# ESP32_With_USB_C_3rd.net
KiCad netlist of a schematic drawn in Altium Designer
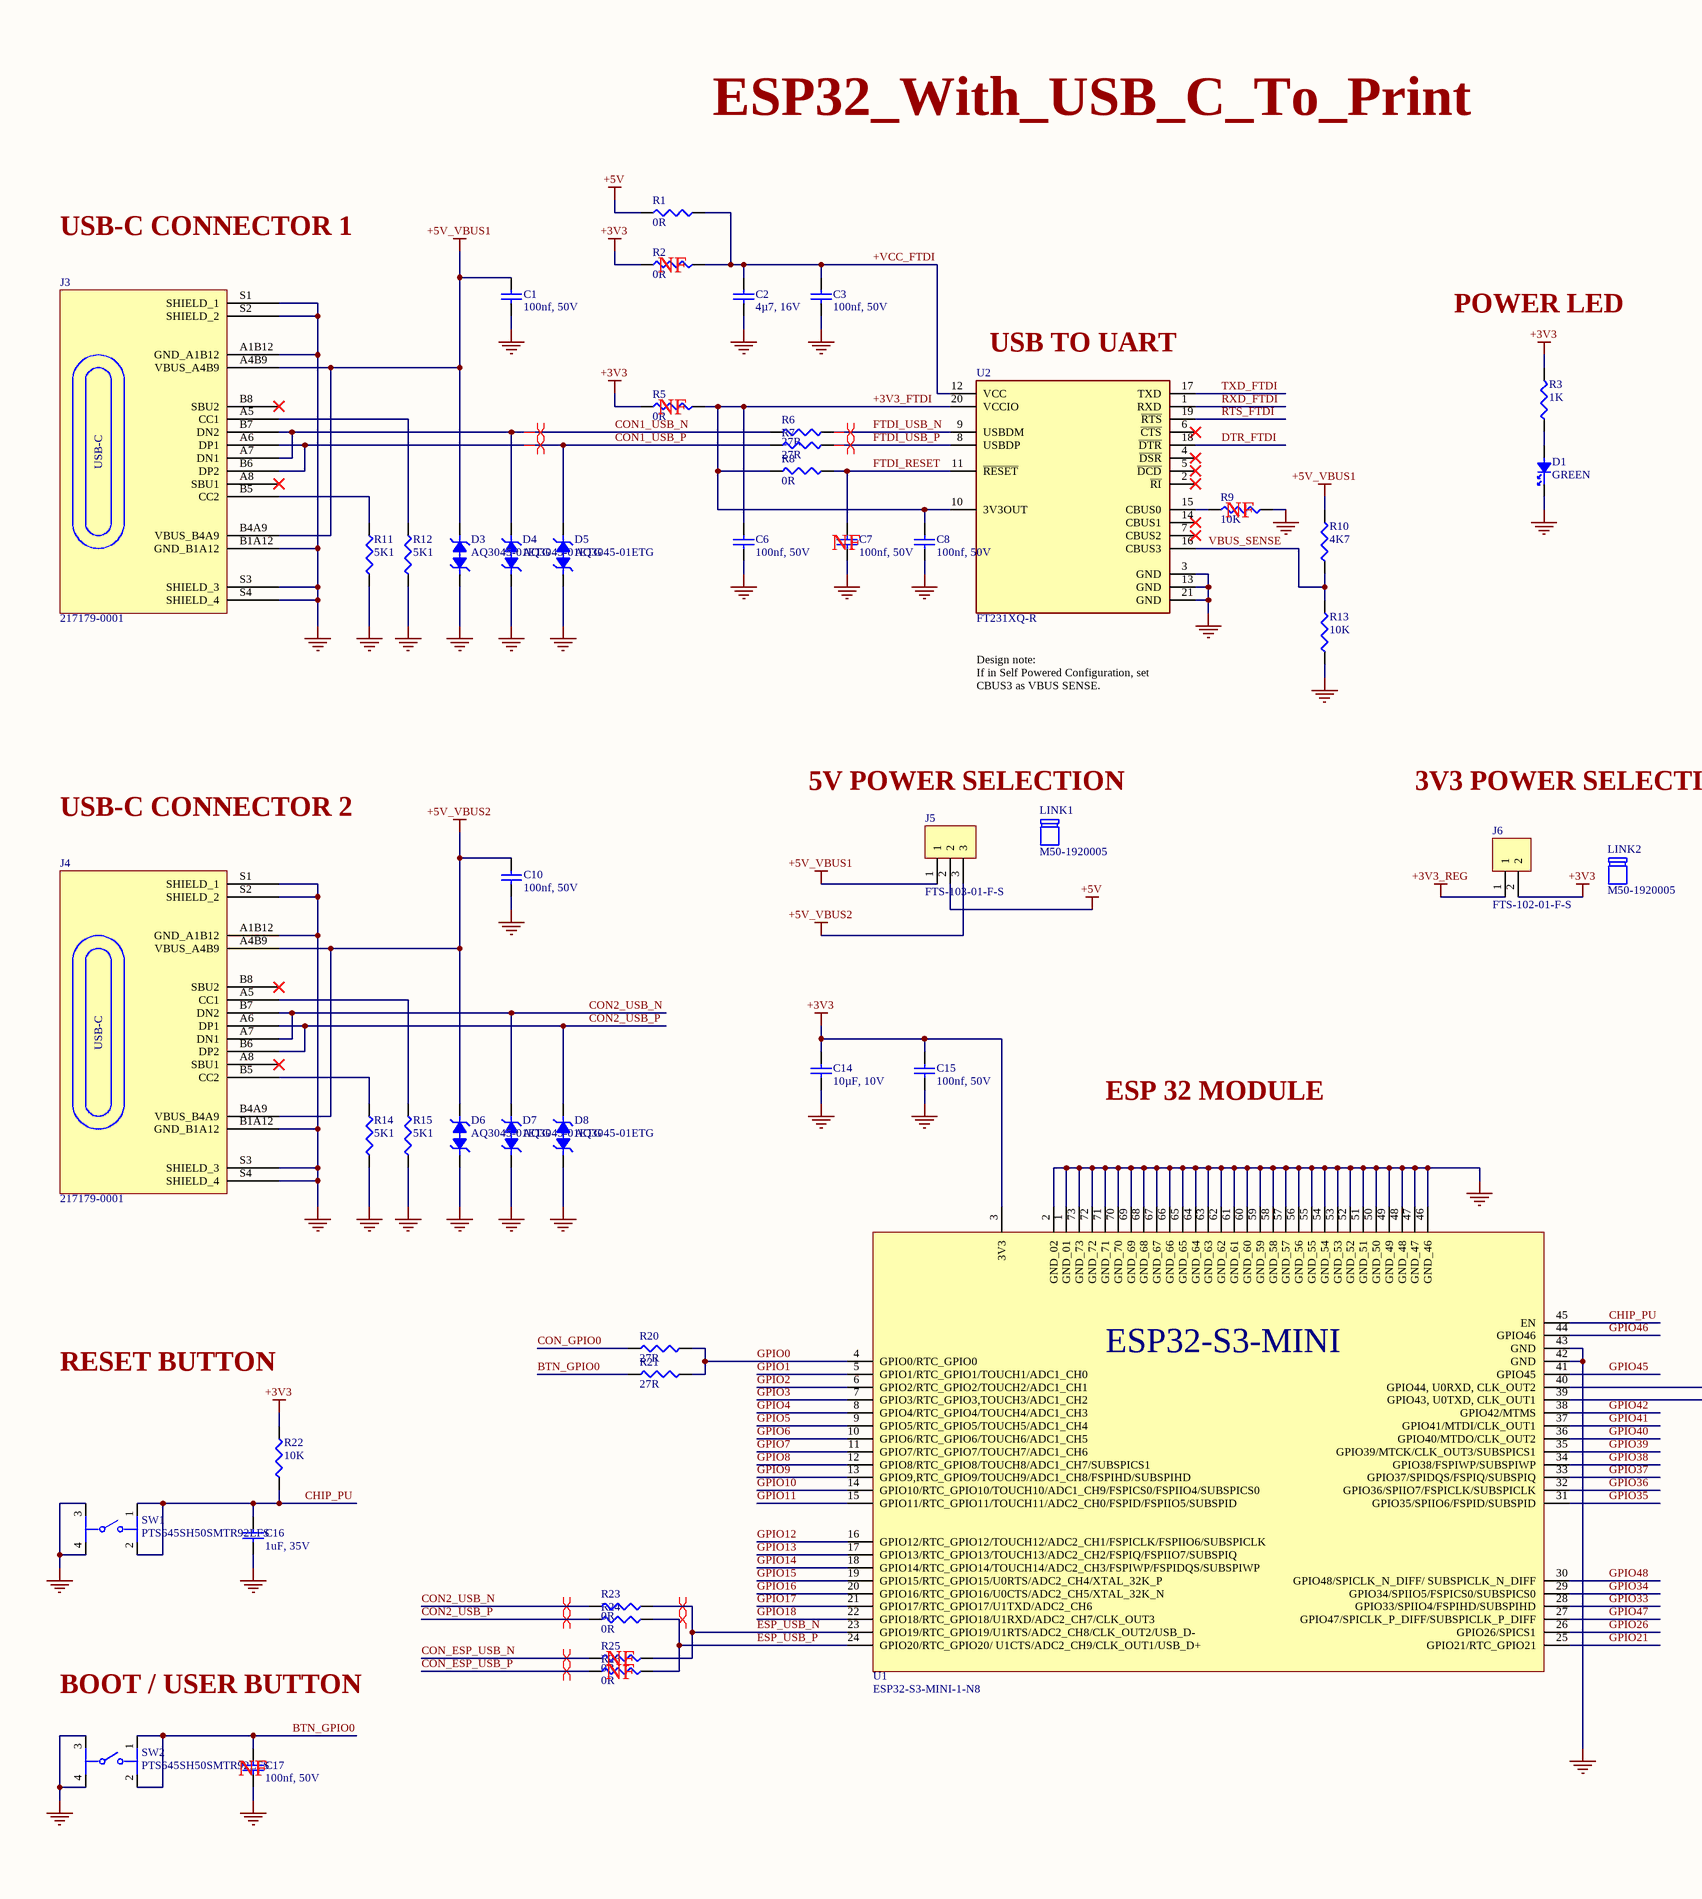
[diagram p0: ESP32 With USB C 3rd.SchDoc, left]
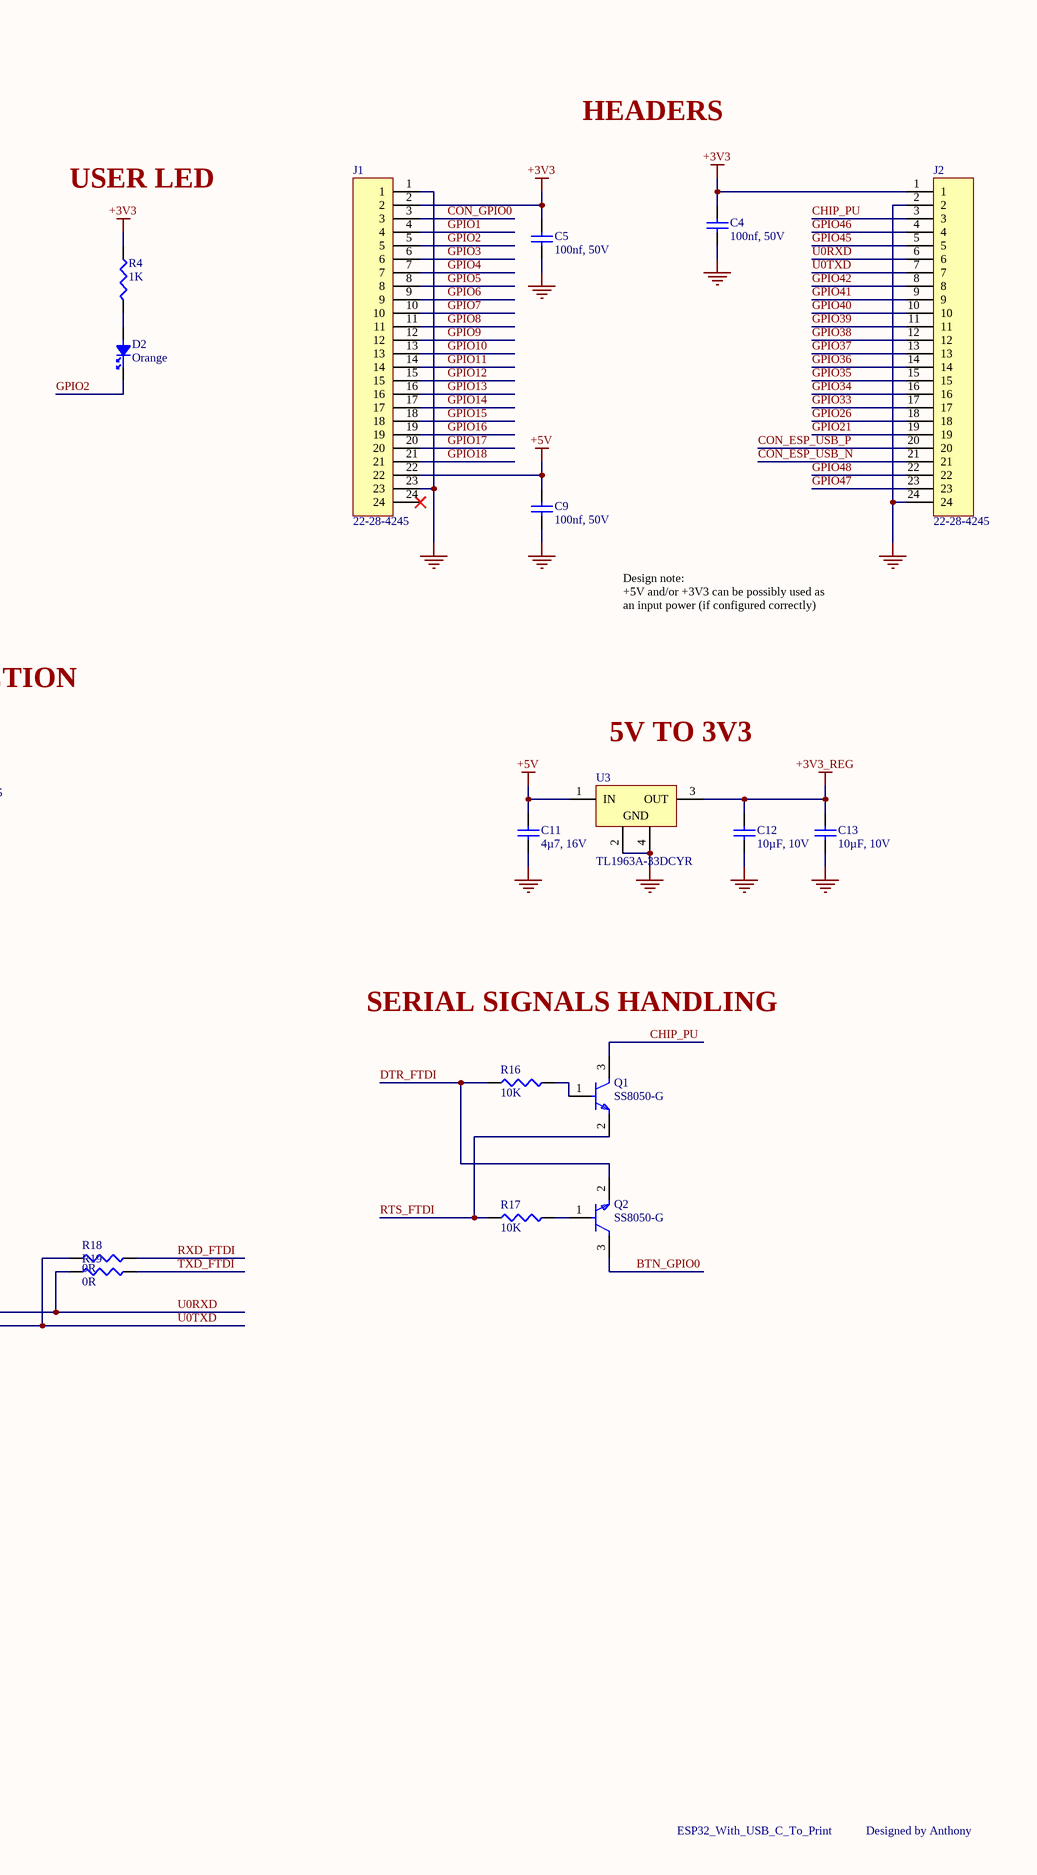
[diagram p1: ESP32 With USB C 3rd.SchDoc, right]

(export (version "E")
  (design (tool "Eeschema 10.0.6"))
  (components
    (comp (ref "C1")
      (value "100nf, 50V")
      (footprint "CAPC1005X65N")
      (description "CAP CER 0.1UF 50V X7R 0402")
      (fields
        (field (name "MANUFACTURER") "Samsung")
        (field (name "MANUFACTURER PART NUMBER") "CL05B104KB5NNNC")
      )
      (libsource (lib "Schlib1") (part "CL05B104KB5NNNC"))
    )
    (comp (ref "C2")
      (value "4µ7, 16V")
      (footprint "CAPC1005X65N")
      (description "CAP CER 4.7UF 16V X5R 0402")
      (fields
        (field (name "MANUFACTURER") "Samsung")
        (field (name "MANUFACTURER PART NUMBER") "CL05A475MO5NUNC")
      )
      (libsource (lib "Schlib1") (part "CL05A475MO5NUNC"))
    )
    (comp (ref "C3")
      (value "100nf, 50V")
      (footprint "CAPC1005X65N")
      (description "CAP CER 0.1UF 50V X7R 0402")
      (fields
        (field (name "MANUFACTURER") "Samsung")
        (field (name "MANUFACTURER PART NUMBER") "CL05B104KB5NNNC")
      )
      (libsource (lib "Schlib1") (part "CL05B104KB5NNNC"))
    )
    (comp (ref "C4")
      (value "100nf, 50V")
      (footprint "CAPC1005X65N")
      (description "CAP CER 0.1UF 50V X7R 0402")
      (fields
        (field (name "MANUFACTURER") "Samsung")
        (field (name "MANUFACTURER PART NUMBER") "CL05B104KB5NNNC")
      )
      (libsource (lib "Schlib1") (part "CL05B104KB5NNNC"))
    )
    (comp (ref "C5")
      (value "100nf, 50V")
      (footprint "CAPC1005X65N")
      (description "CAP CER 0.1UF 50V X7R 0402")
      (fields
        (field (name "MANUFACTURER") "Samsung")
        (field (name "MANUFACTURER PART NUMBER") "CL05B104KB5NNNC")
      )
      (libsource (lib "Schlib1") (part "CL05B104KB5NNNC"))
    )
    (comp (ref "C6")
      (value "100nf, 50V")
      (footprint "CAPC1005X65N")
      (description "CAP CER 0.1UF 50V X7R 0402")
      (fields
        (field (name "MANUFACTURER") "Samsung")
        (field (name "MANUFACTURER PART NUMBER") "CL05B104KB5NNNC")
      )
      (libsource (lib "Schlib1") (part "CL05B104KB5NNNC"))
    )
    (comp (ref "C7")
      (value "100nf, 50V")
      (footprint "CAPC1005X65N")
      (description "CAP CER 0.1UF 50V X7R 0402")
      (fields
        (field (name "MANUFACTURER") "Samsung")
        (field (name "MANUFACTURER PART NUMBER") "CL05B104KB5NNNC")
      )
      (libsource (lib "Schlib1") (part "CL05B104KB5NNNC"))
    )
    (comp (ref "C8")
      (value "100nf, 50V")
      (footprint "CAPC1005X65N")
      (description "CAP CER 0.1UF 50V X7R 0402")
      (fields
        (field (name "MANUFACTURER") "Samsung")
        (field (name "MANUFACTURER PART NUMBER") "CL05B104KB5NNNC")
      )
      (libsource (lib "Schlib1") (part "CL05B104KB5NNNC"))
    )
    (comp (ref "C9")
      (value "100nf, 50V")
      (footprint "CAPC1005X65N")
      (description "CAP CER 0.1UF 50V X7R 0402")
      (fields
        (field (name "MANUFACTURER") "Samsung")
        (field (name "MANUFACTURER PART NUMBER") "CL05B104KB5NNNC")
      )
      (libsource (lib "Schlib1") (part "CL05B104KB5NNNC"))
    )
    (comp (ref "C10")
      (value "100nf, 50V")
      (footprint "CAPC1005X65N")
      (description "CAP CER 0.1UF 50V X7R 0402")
      (fields
        (field (name "MANUFACTURER") "Samsung")
        (field (name "MANUFACTURER PART NUMBER") "CL05B104KB5NNNC")
      )
      (libsource (lib "Schlib1") (part "CL05B104KB5NNNC"))
    )
    (comp (ref "C11")
      (value "4µ7, 16V")
      (footprint "CAPC1005X65N")
      (description "CAP CER 4.7UF 16V X5R 0402")
      (fields
        (field (name "MANUFACTURER") "Samsung")
        (field (name "MANUFACTURER PART NUMBER") "CL05A475MO5NUNC")
      )
      (libsource (lib "Schlib1") (part "CL05A475MO5NUNC"))
    )
    (comp (ref "C12")
      (value "10µF, 10V")
      (footprint "CAPC1005X65N")
      (description "CAP CER 10UF 10V X5R 0402")
      (fields
        (field (name "MANUFACTURER") "Samsung")
        (field (name "MANUFACTURER PART NUMBER") "CL05A106MP5NRNC")
      )
      (libsource (lib "Schlib1") (part "CL05A106MP5NRNC"))
    )
    (comp (ref "C13")
      (value "10µF, 10V")
      (footprint "CAPC1005X65N")
      (description "CAP CER 10UF 10V X5R 0402")
      (fields
        (field (name "MANUFACTURER") "Samsung")
        (field (name "MANUFACTURER PART NUMBER") "CL05A106MP5NRNC")
      )
      (libsource (lib "Schlib1") (part "CL05A106MP5NRNC"))
    )
    (comp (ref "C14")
      (value "10µF, 10V")
      (footprint "CAPC1005X65N")
      (description "CAP CER 10UF 10V X5R 0402")
      (fields
        (field (name "MANUFACTURER") "Samsung")
        (field (name "MANUFACTURER PART NUMBER") "CL05A106MP5NRNC")
      )
      (libsource (lib "Schlib1") (part "CL05A106MP5NRNC"))
    )
    (comp (ref "C15")
      (value "100nf, 50V")
      (footprint "CAPC1005X65N")
      (description "CAP CER 0.1UF 50V X7R 0402")
      (fields
        (field (name "MANUFACTURER") "Samsung")
        (field (name "MANUFACTURER PART NUMBER") "CL05B104KB5NNNC")
      )
      (libsource (lib "Schlib1") (part "CL05B104KB5NNNC"))
    )
    (comp (ref "C16")
      (value "1uF, 35V")
      (footprint "CAPC1005X65N")
      (description "CAP CER 1UF 35V X5R 0402")
      (fields
        (field (name "MANUFACTURER") "Samsung")
        (field (name "MANUFACTURER PART NUMBER") "CL05A105KL5NRNC")
      )
      (libsource (lib "Schlib1") (part "CL05A105KL5NRNC"))
    )
    (comp (ref "C17")
      (value "100nf, 50V")
      (footprint "CAPC1005X65N")
      (description "CAP CER 0.1UF 50V X7R 0402")
      (fields
        (field (name "MANUFACTURER") "Samsung")
        (field (name "MANUFACTURER PART NUMBER") "CL05B104KB5NNNC")
      )
      (libsource (lib "Schlib1") (part "CL05B104KB5NNNC"))
    )
    (comp (ref "D1")
      (value "GREEN")
      (footprint "LED0402G")
      (description "LED YLW-GRN 0402 SMD")
      (fields
        (field (name "MANUFACTURER") "Vishay")
        (field (name "MANUFACTURER PART NUMBER") "VLMG1500-GS08")
      )
      (libsource (lib "Schlib1") (part "VLMG1500-GS08"))
    )
    (comp (ref "D2")
      (value "Orange")
      (footprint "LED0402OR")
      (description "LED ORANGE 0402 SMD")
      (fields
        (field (name "MANUFACTURER") "Vishay")
        (field (name "MANUFACTURER PART NUMBER") "VLMO1500-GS08")
      )
      (libsource (lib "Schlib1") (part "VLMO1500-GS08"))
    )
    (comp (ref "D3")
      (value "AQ3045-01ETG")
      (footprint "SOD882")
      (description "TVS DIODE 5.3VWM 12VC SOD882")
      (fields (field (name "MANUFACTURER") "Littelfuse") (field (name "LCSC PART NUMBER") "C3710326"))
      (libsource (lib "Schlib1") (part "AQ3045-01ETG"))
    )
    (comp (ref "D4")
      (value "AQ3045-01ETG")
      (footprint "SOD882")
      (description "TVS DIODE 5.3VWM 12VC SOD882")
      (fields (field (name "MANUFACTURER") "Littelfuse") (field (name "LCSC PART NUMBER") "C3710326"))
      (libsource (lib "Schlib1") (part "AQ3045-01ETG"))
    )
    (comp (ref "D5")
      (value "AQ3045-01ETG")
      (footprint "SOD882")
      (description "TVS DIODE 5.3VWM 12VC SOD882")
      (fields (field (name "MANUFACTURER") "Littelfuse") (field (name "LCSC PART NUMBER") "C3710326"))
      (libsource (lib "Schlib1") (part "AQ3045-01ETG"))
    )
    (comp (ref "D6")
      (value "AQ3045-01ETG")
      (footprint "SOD882")
      (description "TVS DIODE 5.3VWM 12VC SOD882")
      (fields (field (name "MANUFACTURER") "Littelfuse") (field (name "LCSC PART NUMBER") "C3710326"))
      (libsource (lib "Schlib1") (part "AQ3045-01ETG"))
    )
    (comp (ref "D7")
      (value "AQ3045-01ETG")
      (footprint "SOD882")
      (description "TVS DIODE 5.3VWM 12VC SOD882")
      (fields (field (name "MANUFACTURER") "Littelfuse") (field (name "LCSC PART NUMBER") "C3710326"))
      (libsource (lib "Schlib1") (part "AQ3045-01ETG"))
    )
    (comp (ref "D8")
      (value "AQ3045-01ETG")
      (footprint "SOD882")
      (description "TVS DIODE 5.3VWM 12VC SOD882")
      (fields (field (name "MANUFACTURER") "Littelfuse") (field (name "LCSC PART NUMBER") "C3710326"))
      (libsource (lib "Schlib1") (part "AQ3045-01ETG"))
    )
    (comp (ref "J1")
      (value "22-28-4245")
      (footprint "HDR_1*24_2.54MM")
      (description "CONN HEADER VERT 24POS 2.54MM")
      (fields (field (name "MANUFACTURER") "Molex") (field (name "LCSC PART NUMBER") "C7145888"))
      (libsource (lib "") (part "22-28-4245_1"))
    )
    (comp (ref "J2")
      (value "22-28-4245")
      (footprint "HDR_1*24_2.54MM")
      (description "CONN HEADER VERT 24POS 2.54MM")
      (fields (field (name "MANUFACTURER") "Molex") (field (name "LCSC PART NUMBER") "C7145888"))
      (libsource (lib "Schlib1") (part "22-28-4245"))
    )
    (comp (ref "J3")
      (value "217179-0001")
      (footprint "FP-2171790001-MFG")
      (description "CONN RCP USB2.0 TYP C 24P SMD RA")
      (fields (field (name "MANUFACTURER") "Molex") (field (name "LCSC PART NUMBER") "C3197684"))
      (libsource (lib "Schlib1") (part "217179-0001"))
    )
    (comp (ref "J4")
      (value "217179-0001")
      (footprint "FP-2171790001-MFG")
      (description "CONN RCP USB2.0 TYP C 24P SMD RA")
      (fields (field (name "MANUFACTURER") "Molex") (field (name "LCSC PART NUMBER") "C3197684"))
      (libsource (lib "Schlib1") (part "217179-0001"))
    )
    (comp (ref "J5")
      (value "FTS-103-01-F-S")
      (footprint "HDR_1*3_1.27MM")
      (description "CONN HEADER VERT 3POS 1.27MM")
      (fields (field (name "MANUFACTURER") "Samtec") (field (name "LCSC PART NUMBER") "C3333578"))
      (libsource (lib "Schlib1") (part "FTS-103-01-F-S"))
    )
    (comp (ref "J6")
      (value "FTS-102-01-F-S")
      (footprint "HDR_1*2_1.27MM")
      (description "CONN HEADER VERT 2POS 1.27MM")
      (fields (field (name "MANUFACTURER") "Samtec") (field (name "LCSC PART NUMBER") "C6045317"))
      (libsource (lib "Schlib1") (part "FTS-102-01-F-S"))
    )
    (comp (ref "LINK1")
      (value "M50-1920005")
      (description "CONN SHUNT 1.27MM RED")
      (fields (field (name "MANUFACTURER") "Harwin") (field (name "LCSC PART NUMBER") "C6985646"))
      (libsource (lib "Schlib1") (part "M50-1920005"))
    )
    (comp (ref "LINK2")
      (value "M50-1920005")
      (description "CONN SHUNT 1.27MM RED")
      (fields (field (name "MANUFACTURER") "Harwin") (field (name "LCSC PART NUMBER") "C6985646"))
      (libsource (lib "Schlib1") (part "M50-1920005"))
    )
    (comp (ref "Q1")
      (value "SS8050-G")
      (footprint "FP-SS8050-G-IPC_B")
      (description "TRANS NPN 25V 1.5A SOT-23-3")
      (fields (field (name "MANUFACTURER") "Comchip") (field (name "LCSC PART NUMBER") "C164886"))
      (libsource (lib "Schlib1") (part "SS8050-G"))
    )
    (comp (ref "Q2")
      (value "SS8050-G")
      (footprint "FP-SS8050-G-IPC_B")
      (description "TRANS NPN 25V 1.5A SOT-23-3")
      (fields (field (name "MANUFACTURER") "Comchip") (field (name "LCSC PART NUMBER") "C164886"))
      (libsource (lib "Schlib1") (part "SS8050-G"))
    )
    (comp (ref "R1")
      (value "0R")
      (footprint "RESC1005X37N")
      (description "RES 0 OHM JUMPER 1/16W 0402")
      (fields
        (field (name "MANUFACTURER") "Yageo")
        (field (name "MANUFACTURER PART NUMBER") "RC0402JR-070RL")
      )
      (libsource (lib "Schlib1") (part "RC0402JR-070RL"))
    )
    (comp (ref "R2")
      (value "0R")
      (footprint "RESC1005X37N")
      (description "RES 0 OHM JUMPER 1/16W 0402")
      (fields
        (field (name "MANUFACTURER") "Yageo")
        (field (name "MANUFACTURER PART NUMBER") "RC0402JR-070RL")
      )
      (libsource (lib "Schlib1") (part "RC0402JR-070RL"))
    )
    (comp (ref "R3")
      (value "1K")
      (footprint "RESC1005X37N")
      (description "RES 1K OHM 1% 1/16W 0402")
      (fields
        (field (name "MANUFACTURER") "Yageo")
        (field (name "MANUFACTURER PART NUMBER") "RC0402FR-071KL")
      )
      (libsource (lib "Schlib1") (part "RC0402FR-071KL"))
    )
    (comp (ref "R4")
      (value "1K")
      (footprint "RESC1005X37N")
      (description "RES 1K OHM 1% 1/16W 0402")
      (fields
        (field (name "MANUFACTURER") "Yageo")
        (field (name "MANUFACTURER PART NUMBER") "RC0402FR-071KL")
      )
      (libsource (lib "Schlib1") (part "RC0402FR-071KL"))
    )
    (comp (ref "R5")
      (value "0R")
      (footprint "RESC1005X37N")
      (description "RES 0 OHM JUMPER 1/16W 0402")
      (fields
        (field (name "MANUFACTURER") "Yageo")
        (field (name "MANUFACTURER PART NUMBER") "RC0402JR-070RL")
      )
      (libsource (lib "Schlib1") (part "RC0402JR-070RL"))
    )
    (comp (ref "R6")
      (value "27R")
      (footprint "RESC1005X37N")
      (description "RES 27 OHM 1% 1/16W 0402")
      (fields
        (field (name "MANUFACTURER") "Yageo")
        (field (name "MANUFACTURER PART NUMBER") "RC0402FR-0727RL")
      )
      (libsource (lib "Schlib1") (part "RC0402FR-0727RL"))
    )
    (comp (ref "R7")
      (value "27R")
      (footprint "RESC1005X37N")
      (description "RES 27 OHM 1% 1/16W 0402")
      (fields
        (field (name "MANUFACTURER") "Yageo")
        (field (name "MANUFACTURER PART NUMBER") "RC0402FR-0727RL")
      )
      (libsource (lib "Schlib1") (part "RC0402FR-0727RL"))
    )
    (comp (ref "R8")
      (value "0R")
      (footprint "RESC1005X37N")
      (description "RES 0 OHM JUMPER 1/16W 0402")
      (fields
        (field (name "MANUFACTURER") "Yageo")
        (field (name "MANUFACTURER PART NUMBER") "RC0402JR-070RL")
      )
      (libsource (lib "Schlib1") (part "RC0402JR-070RL"))
    )
    (comp (ref "R9")
      (value "10K")
      (footprint "RESC1005X37N")
      (description "RES 10 KOHM 1% 1/8W 0402")
      (fields
        (field (name "MANUFACTURER") "Yageo")
        (field (name "MANUFACTURER PART NUMBER") "AC0402FR-7W10KL")
      )
      (libsource (lib "Schlib1") (part "AC0402FR-7W10KL"))
    )
    (comp (ref "R10")
      (value "4K7")
      (footprint "RESC1005X37N")
      (description "RES 4.7K OHM 1% 1/16W 0402")
      (fields
        (field (name "MANUFACTURER") "Yageo")
        (field (name "MANUFACTURER PART NUMBER") "RC0402FR-074K7L")
      )
      (libsource (lib "Schlib1") (part "RC0402FR-074K7L"))
    )
    (comp (ref "R11")
      (value "5K1")
      (footprint "RESC1005X37N")
      (description "RES SMD 5.1K OHM 1% 1/16W 0402")
      (fields
        (field (name "MANUFACTURER") "Yageo")
        (field (name "MANUFACTURER PART NUMBER") "AC0402FR-075K1L")
      )
      (libsource (lib "Schlib1") (part "AC0402FR-075K1L"))
    )
    (comp (ref "R12")
      (value "5K1")
      (footprint "RESC1005X37N")
      (description "RES SMD 5.1K OHM 1% 1/16W 0402")
      (fields
        (field (name "MANUFACTURER") "Yageo")
        (field (name "MANUFACTURER PART NUMBER") "AC0402FR-075K1L")
      )
      (libsource (lib "Schlib1") (part "AC0402FR-075K1L"))
    )
    (comp (ref "R13")
      (value "10K")
      (footprint "RESC1005X37N")
      (description "RES 10 KOHM 1% 1/8W 0402")
      (fields
        (field (name "MANUFACTURER") "Yageo")
        (field (name "MANUFACTURER PART NUMBER") "AC0402FR-7W10KL")
      )
      (libsource (lib "Schlib1") (part "AC0402FR-7W10KL"))
    )
    (comp (ref "R14")
      (value "5K1")
      (footprint "RESC1005X37N")
      (description "RES SMD 5.1K OHM 1% 1/16W 0402")
      (fields
        (field (name "MANUFACTURER") "Yageo")
        (field (name "MANUFACTURER PART NUMBER") "AC0402FR-075K1L")
      )
      (libsource (lib "Schlib1") (part "AC0402FR-075K1L"))
    )
    (comp (ref "R15")
      (value "5K1")
      (footprint "RESC1005X37N")
      (description "RES SMD 5.1K OHM 1% 1/16W 0402")
      (fields
        (field (name "MANUFACTURER") "Yageo")
        (field (name "MANUFACTURER PART NUMBER") "AC0402FR-075K1L")
      )
      (libsource (lib "Schlib1") (part "AC0402FR-075K1L"))
    )
    (comp (ref "R16")
      (value "10K")
      (footprint "RESC1005X37N")
      (description "RES 10 KOHM 1% 1/8W 0402")
      (fields
        (field (name "MANUFACTURER") "Yageo")
        (field (name "MANUFACTURER PART NUMBER") "AC0402FR-7W10KL")
      )
      (libsource (lib "Schlib1") (part "AC0402FR-7W10KL"))
    )
    (comp (ref "R17")
      (value "10K")
      (footprint "RESC1005X37N")
      (description "RES 10 KOHM 1% 1/8W 0402")
      (fields
        (field (name "MANUFACTURER") "Yageo")
        (field (name "MANUFACTURER PART NUMBER") "AC0402FR-7W10KL")
      )
      (libsource (lib "Schlib1") (part "AC0402FR-7W10KL"))
    )
    (comp (ref "R18")
      (value "0R")
      (footprint "RESC1005X37N")
      (description "RES 0 OHM JUMPER 1/16W 0402")
      (fields
        (field (name "MANUFACTURER") "Yageo")
        (field (name "MANUFACTURER PART NUMBER") "RC0402JR-070RL")
      )
      (libsource (lib "Schlib1") (part "RC0402JR-070RL"))
    )
    (comp (ref "R19")
      (value "0R")
      (footprint "RESC1005X37N")
      (description "RES 0 OHM JUMPER 1/16W 0402")
      (fields
        (field (name "MANUFACTURER") "Yageo")
        (field (name "MANUFACTURER PART NUMBER") "RC0402JR-070RL")
      )
      (libsource (lib "Schlib1") (part "RC0402JR-070RL"))
    )
    (comp (ref "R20")
      (value "27R")
      (footprint "RESC1005X37N")
      (description "RES 27 OHM 1% 1/16W 0402")
      (fields
        (field (name "MANUFACTURER") "Yageo")
        (field (name "MANUFACTURER PART NUMBER") "RC0402FR-0727RL")
      )
      (libsource (lib "Schlib1") (part "RC0402FR-0727RL"))
    )
    (comp (ref "R21")
      (value "27R")
      (footprint "RESC1005X37N")
      (description "RES 27 OHM 1% 1/16W 0402")
      (fields
        (field (name "MANUFACTURER") "Yageo")
        (field (name "MANUFACTURER PART NUMBER") "RC0402FR-0727RL")
      )
      (libsource (lib "Schlib1") (part "RC0402FR-0727RL"))
    )
    (comp (ref "R22")
      (value "10K")
      (footprint "RESC1005X37N")
      (description "RES 10 KOHM 1% 1/8W 0402")
      (fields
        (field (name "MANUFACTURER") "Yageo")
        (field (name "MANUFACTURER PART NUMBER") "AC0402FR-7W10KL")
      )
      (libsource (lib "Schlib1") (part "AC0402FR-7W10KL"))
    )
    (comp (ref "R23")
      (value "0R")
      (footprint "RESC1005X37N")
      (description "RES 0 OHM JUMPER 1/16W 0402")
      (fields
        (field (name "MANUFACTURER") "Yageo")
        (field (name "MANUFACTURER PART NUMBER") "RC0402JR-070RL")
      )
      (libsource (lib "Schlib1") (part "RC0402JR-070RL"))
    )
    (comp (ref "R24")
      (value "0R")
      (footprint "RESC1005X37N")
      (description "RES 0 OHM JUMPER 1/16W 0402")
      (fields
        (field (name "MANUFACTURER") "Yageo")
        (field (name "MANUFACTURER PART NUMBER") "RC0402JR-070RL")
      )
      (libsource (lib "Schlib1") (part "RC0402JR-070RL"))
    )
    (comp (ref "R25")
      (value "0R")
      (footprint "RESC1005X37N")
      (description "RES 0 OHM JUMPER 1/16W 0402")
      (fields
        (field (name "MANUFACTURER") "Yageo")
        (field (name "MANUFACTURER PART NUMBER") "RC0402JR-070RL")
      )
      (libsource (lib "Schlib1") (part "RC0402JR-070RL"))
    )
    (comp (ref "R26")
      (value "0R")
      (footprint "RESC1005X37N")
      (description "RES 0 OHM JUMPER 1/16W 0402")
      (fields
        (field (name "MANUFACTURER") "Yageo")
        (field (name "MANUFACTURER PART NUMBER") "RC0402JR-070RL")
      )
      (libsource (lib "Schlib1") (part "RC0402JR-070RL"))
    )
    (comp (ref "SW1")
      (value "PTS645SH50SMTR92LFS")
      (footprint "FP-PTS645SH50SMTR92LFS-MFG")
      (description "SWITCH TACTILE SPST-NO 0.05A 12V")
      (fields (field (name "MANUFACTURER") "ITT C&K") (field (name "LCSC PART NUMBER") "C221869"))
      (libsource (lib "Schlib1") (part "PTS645SH50SMTR92LFS"))
    )
    (comp (ref "SW2")
      (value "PTS645SH50SMTR92LFS")
      (footprint "FP-PTS645SH50SMTR92LFS-MFG")
      (description "SWITCH TACTILE SPST-NO 0.05A 12V")
      (fields (field (name "MANUFACTURER") "ITT C&K") (field (name "LCSC PART NUMBER") "C221869"))
      (libsource (lib "Schlib1") (part "PTS645SH50SMTR92LFS"))
    )
    (comp (ref "U1")
      (value "ESP32-S3-MINI-1-N8")
      (footprint "XCVR_ESP32-S3-MINI-1-N8")
      (description "20.5dBm ESP32-S3FN8 Chip 2.4GHz SMD WiFi Modules ROHS")
      (fields (field (name "MANUFACTURER") "Espressif Systems") (field (name "LCSC PART NUMBER") "C2913206"))
      (libsource (lib "Schlib1") (part "ESP32-S3-MINI-1-N8"))
    )
    (comp (ref "U2")
      (value "FT231XQ-R")
      (footprint "FP-QFN-20-IPC_B")
      (description "IC USB SERIAL FULL UART 20QFN")
      (fields (field (name "MANUFACTURER") "FTDI") (field (name "LCSC PART NUMBER") "C132159"))
      (libsource (lib "Schlib1") (part "FT231XQ-R"))
    )
    (comp (ref "U3")
      (value "TL1963A-33DCYR")
      (footprint "DCY0004A_N")
      (description "IC REG LIN 3.3V 1.5A SOT-223-4")
      (fields (field (name "MANUFACTURER") "Texas Instruments") (field (name "LCSC PART NUMBER") "C181262"))
      (libsource (lib "Schlib1") (part "TL1963A-33DCYR"))
    )
  )
  (nets
    (net (code "1") (name "+3V3") (class "Default")
      (node (ref "C14") (pin "2") (pinfunction "2_2") (pintype "passive"))
      (node (ref "C15") (pin "1") (pinfunction "1_1") (pintype "passive"))
      (node (ref "C4") (pin "1") (pinfunction "1_1") (pintype "passive"))
      (node (ref "C5") (pin "1") (pinfunction "1_1") (pintype "passive"))
      (node (ref "J1") (pin "2") (pinfunction "2_2") (pintype "passive"))
      (node (ref "J2") (pin "1") (pinfunction "1_1") (pintype "passive"))
      (node (ref "J6") (pin "2") (pinfunction "2_2") (pintype "passive"))
      (node (ref "R2") (pin "1") (pinfunction "1_1") (pintype "passive"))
      (node (ref "R22") (pin "2") (pinfunction "2_2") (pintype "passive"))
      (node (ref "R3") (pin "2") (pinfunction "2_2") (pintype "passive"))
      (node (ref "R4") (pin "2") (pinfunction "2_2") (pintype "passive"))
      (node (ref "R5") (pin "1") (pinfunction "1_1") (pintype "passive"))
      (node (ref "U1") (pin "3") (pinfunction "3V3_3") (pintype "passive"))
    )
    (net (code "2") (name "+3V3_REG") (class "Default")
      (node (ref "C12") (pin "2") (pinfunction "2_2") (pintype "passive"))
      (node (ref "C13") (pin "2") (pinfunction "2_2") (pintype "passive"))
      (node (ref "J6") (pin "1") (pinfunction "1_1") (pintype "passive"))
      (node (ref "U3") (pin "3") (pinfunction "OUT_3") (pintype "power_in"))
    )
    (net (code "3") (name "+5V") (class "Default")
      (node (ref "C11") (pin "2") (pinfunction "2_2") (pintype "passive"))
      (node (ref "C9") (pin "1") (pinfunction "1_1") (pintype "passive"))
      (node (ref "J1") (pin "22") (pinfunction "22_22") (pintype "passive"))
      (node (ref "J5") (pin "2") (pinfunction "2_2") (pintype "passive"))
      (node (ref "R1") (pin "1") (pinfunction "1_1") (pintype "passive"))
      (node (ref "U3") (pin "1") (pinfunction "IN_1") (pintype "power_in"))
    )
    (net (code "4") (name "+5V_VBUS1") (class "Default")
      (node (ref "C1") (pin "1") (pinfunction "1_1") (pintype "passive"))
      (node (ref "D3") (pin "1") (pinfunction "1_1") (pintype "passive"))
      (node (ref "J3") (pin "A4B9") (pinfunction "VBUS_A4B9_A4B9") (pintype "passive"))
      (node (ref "J3") (pin "B4A9") (pinfunction "VBUS_B4A9_B4A9") (pintype "passive"))
      (node (ref "J5") (pin "1") (pinfunction "1_1") (pintype "passive"))
      (node (ref "R10") (pin "1") (pinfunction "1_1") (pintype "passive"))
    )
    (net (code "5") (name "+5V_VBUS2") (class "Default")
      (node (ref "C10") (pin "1") (pinfunction "1_1") (pintype "passive"))
      (node (ref "D6") (pin "1") (pinfunction "1_1") (pintype "passive"))
      (node (ref "J4") (pin "A4B9") (pinfunction "VBUS_A4B9_A4B9") (pintype "passive"))
      (node (ref "J4") (pin "B4A9") (pinfunction "VBUS_B4A9_B4A9") (pintype "passive"))
      (node (ref "J5") (pin "3") (pinfunction "3_3") (pintype "passive"))
    )
    (net (code "6") (name "/+3V3_FTDI") (class "Default")
      (node (ref "C6") (pin "1") (pinfunction "1_1") (pintype "passive"))
      (node (ref "C8") (pin "1") (pinfunction "1_1") (pintype "passive"))
      (node (ref "R5") (pin "2") (pinfunction "2_2") (pintype "passive"))
      (node (ref "R8") (pin "1") (pinfunction "1_1") (pintype "passive"))
      (node (ref "U2") (pin "10") (pinfunction "3V3OUT_10") (pintype "passive"))
      (node (ref "U2") (pin "20") (pinfunction "VCCIO_20") (pintype "passive"))
    )
    (net (code "7") (name "/+VCC_FTDI") (class "Default")
      (node (ref "C2") (pin "2") (pinfunction "2_2") (pintype "passive"))
      (node (ref "C3") (pin "1") (pinfunction "1_1") (pintype "passive"))
      (node (ref "R1") (pin "2") (pinfunction "2_2") (pintype "passive"))
      (node (ref "R2") (pin "2") (pinfunction "2_2") (pintype "passive"))
      (node (ref "U2") (pin "12") (pinfunction "VCC_12") (pintype "passive"))
    )
    (net (code "8") (name "/BTN_GPIO0") (class "Default")
      (node (ref "C17") (pin "1") (pinfunction "1_1") (pintype "passive"))
      (node (ref "Q2") (pin "3") (pinfunction "C_3") (pintype "passive"))
      (node (ref "R21") (pin "1") (pinfunction "1_1") (pintype "passive"))
      (node (ref "SW2") (pin "1") (pinfunction "1_1") (pintype "passive"))
      (node (ref "SW2") (pin "2") (pinfunction "2_2") (pintype "passive"))
    )
    (net (code "9") (name "/CHIP_PU") (class "Default")
      (node (ref "C16") (pin "1") (pinfunction "1_1") (pintype "passive"))
      (node (ref "J2") (pin "3") (pinfunction "3_3") (pintype "passive"))
      (node (ref "Q1") (pin "3") (pinfunction "C_3") (pintype "passive"))
      (node (ref "R22") (pin "1") (pinfunction "1_1") (pintype "passive"))
      (node (ref "SW1") (pin "1") (pinfunction "1_1") (pintype "passive"))
      (node (ref "SW1") (pin "2") (pinfunction "2_2") (pintype "passive"))
      (node (ref "U1") (pin "45") (pinfunction "EN_45") (pintype "passive"))
    )
    (net (code "10") (name "/CON1_USB_N") (class "Default")
      (node (ref "D4") (pin "1") (pinfunction "1_1") (pintype "passive"))
      (node (ref "J3") (pin "A7") (pinfunction "DN1_A7") (pintype "passive"))
      (node (ref "J3") (pin "B7") (pinfunction "DN2_B7") (pintype "passive"))
      (node (ref "R6") (pin "1") (pinfunction "1_1") (pintype "passive"))
    )
    (net (code "11") (name "/CON1_USB_P") (class "Default")
      (node (ref "D5") (pin "1") (pinfunction "1_1") (pintype "passive"))
      (node (ref "J3") (pin "A6") (pinfunction "DP1_A6") (pintype "passive"))
      (node (ref "J3") (pin "B6") (pinfunction "DP2_B6") (pintype "passive"))
      (node (ref "R7") (pin "1") (pinfunction "1_1") (pintype "passive"))
    )
    (net (code "12") (name "/CON2_USB_N") (class "Default")
      (node (ref "D7") (pin "1") (pinfunction "1_1") (pintype "passive"))
      (node (ref "J4") (pin "A7") (pinfunction "DN1_A7") (pintype "passive"))
      (node (ref "J4") (pin "B7") (pinfunction "DN2_B7") (pintype "passive"))
      (node (ref "R23") (pin "1") (pinfunction "1_1") (pintype "passive"))
    )
    (net (code "13") (name "/CON2_USB_P") (class "Default")
      (node (ref "D8") (pin "1") (pinfunction "1_1") (pintype "passive"))
      (node (ref "J4") (pin "A6") (pinfunction "DP1_A6") (pintype "passive"))
      (node (ref "J4") (pin "B6") (pinfunction "DP2_B6") (pintype "passive"))
      (node (ref "R24") (pin "1") (pinfunction "1_1") (pintype "passive"))
    )
    (net (code "14") (name "/CON_ESP_USB_N") (class "Default")
      (node (ref "J2") (pin "21") (pinfunction "21_21") (pintype "passive"))
      (node (ref "R25") (pin "1") (pinfunction "1_1") (pintype "passive"))
    )
    (net (code "15") (name "/CON_ESP_USB_P") (class "Default")
      (node (ref "J2") (pin "20") (pinfunction "20_20") (pintype "passive"))
      (node (ref "R26") (pin "1") (pinfunction "1_1") (pintype "passive"))
    )
    (net (code "16") (name "/CON_GPIO0") (class "Default")
      (node (ref "J1") (pin "3") (pinfunction "3_3") (pintype "passive"))
      (node (ref "R20") (pin "1") (pinfunction "1_1") (pintype "passive"))
    )
    (net (code "17") (name "/DTR_FTDI") (class "Default")
      (node (ref "Q2") (pin "2") (pinfunction "E_2") (pintype "passive"))
      (node (ref "R16") (pin "1") (pinfunction "1_1") (pintype "passive"))
      (node (ref "U2") (pin "18") (pinfunction "~{DTR}_18") (pintype "passive"))
    )
    (net (code "18") (name "/ESP_USB_N") (class "Default")
      (node (ref "R23") (pin "2") (pinfunction "2_2") (pintype "passive"))
      (node (ref "R25") (pin "2") (pinfunction "2_2") (pintype "passive"))
      (node (ref "U1") (pin "23") (pinfunction "GPIO19/RTC_GPIO19/U1RTS/ADC2_CH8/CLK_OUT2/USB_D-_23") (pintype "passive"))
    )
    (net (code "19") (name "/ESP_USB_P") (class "Default")
      (node (ref "R24") (pin "2") (pinfunction "2_2") (pintype "passive"))
      (node (ref "R26") (pin "2") (pinfunction "2_2") (pintype "passive"))
      (node (ref "U1") (pin "24") (pinfunction "GPIO20/RTC_GPIO20/_U1CTS/ADC2_CH9/CLK_OUT1/USB_D+_24") (pintype "passive"))
    )
    (net (code "20") (name "/FTDI_RESET") (class "Default")
      (node (ref "C7") (pin "1") (pinfunction "1_1") (pintype "passive"))
      (node (ref "R8") (pin "2") (pinfunction "2_2") (pintype "passive"))
      (node (ref "U2") (pin "11") (pinfunction "~{RESET}_11") (pintype "passive"))
    )
    (net (code "21") (name "/FTDI_USB_N") (class "Default")
      (node (ref "R6") (pin "2") (pinfunction "2_2") (pintype "passive"))
      (node (ref "U2") (pin "9") (pinfunction "USBDM_9") (pintype "passive"))
    )
    (net (code "22") (name "/FTDI_USB_P") (class "Default")
      (node (ref "R7") (pin "2") (pinfunction "2_2") (pintype "passive"))
      (node (ref "U2") (pin "8") (pinfunction "USBDP_8") (pintype "passive"))
    )
    (net (code "23") (name "/GPIO0") (class "Default")
      (node (ref "R20") (pin "2") (pinfunction "2_2") (pintype "passive"))
      (node (ref "R21") (pin "2") (pinfunction "2_2") (pintype "passive"))
      (node (ref "U1") (pin "4") (pinfunction "GPIO0/RTC_GPIO0_4") (pintype "passive"))
    )
    (net (code "24") (name "/GPIO1") (class "Default")
      (node (ref "J1") (pin "4") (pinfunction "4_4") (pintype "passive"))
      (node (ref "U1") (pin "5") (pinfunction "GPIO1/RTC_GPIO1/TOUCH1/ADC1_CH0_5") (pintype "passive"))
    )
    (net (code "25") (name "/GPIO2") (class "Default")
      (node (ref "D2") (pin "1") (pinfunction "1_1") (pintype "passive"))
      (node (ref "J1") (pin "5") (pinfunction "5_5") (pintype "passive"))
      (node (ref "U1") (pin "6") (pinfunction "GPIO2/RTC_GPIO2/TOUCH2/ADC1_CH1_6") (pintype "passive"))
    )
    (net (code "26") (name "/GPIO3") (class "Default")
      (node (ref "J1") (pin "6") (pinfunction "6_6") (pintype "passive"))
      (node (ref "U1") (pin "7") (pinfunction "GPIO3/RTC_GPIO3,TOUCH3/ADC1_CH2_7") (pintype "passive"))
    )
    (net (code "27") (name "/GPIO4") (class "Default")
      (node (ref "J1") (pin "7") (pinfunction "7_7") (pintype "passive"))
      (node (ref "U1") (pin "8") (pinfunction "GPIO4/RTC_GPIO4/TOUCH4/ADC1_CH3_8") (pintype "passive"))
    )
    (net (code "28") (name "/GPIO5") (class "Default")
      (node (ref "J1") (pin "8") (pinfunction "8_8") (pintype "passive"))
      (node (ref "U1") (pin "9") (pinfunction "GPIO5/RTC_GPIO5/TOUCH5/ADC1_CH4_9") (pintype "passive"))
    )
    (net (code "29") (name "/GPIO6") (class "Default")
      (node (ref "J1") (pin "9") (pinfunction "9_9") (pintype "passive"))
      (node (ref "U1") (pin "10") (pinfunction "GPIO6/RTC_GPIO6/TOUCH6/ADC1_CH5_10") (pintype "passive"))
    )
    (net (code "30") (name "/GPIO7") (class "Default")
      (node (ref "J1") (pin "10") (pinfunction "10_10") (pintype "passive"))
      (node (ref "U1") (pin "11") (pinfunction "GPIO7/RTC_GPIO7/TOUCH7/ADC1_CH6_11") (pintype "passive"))
    )
    (net (code "31") (name "/GPIO8") (class "Default")
      (node (ref "J1") (pin "11") (pinfunction "11_11") (pintype "passive"))
      (node (ref "U1") (pin "12") (pinfunction "GPIO8/RTC_GPIO8/TOUCH8/ADC1_CH7/SUBSPICS1_12") (pintype "passive"))
    )
    (net (code "32") (name "/GPIO9") (class "Default")
      (node (ref "J1") (pin "12") (pinfunction "12_12") (pintype "passive"))
      (node (ref "U1") (pin "13") (pinfunction "GPIO9,RTC_GPIO9/TOUCH9/ADC1_CH8/FSPIHD/SUBSPIHD_13") (pintype "passive"))
    )
    (net (code "33") (name "/GPIO10") (class "Default")
      (node (ref "J1") (pin "13") (pinfunction "13_13") (pintype "passive"))
      (node (ref "U1") (pin "14") (pinfunction "GPIO10/RTC_GPIO10/TOUCH10/ADC1_CH9/FSPICS0/FSPIIO4/SUBSPICS0_14") (pintype "passive"))
    )
    (net (code "34") (name "/GPIO11") (class "Default")
      (node (ref "J1") (pin "14") (pinfunction "14_14") (pintype "passive"))
      (node (ref "U1") (pin "15") (pinfunction "GPIO11/RTC_GPIO11/TOUCH11/ADC2_CH0/FSPID/FSPIIO5/SUBSPID_15") (pintype "passive"))
    )
    (net (code "35") (name "/GPIO12") (class "Default")
      (node (ref "J1") (pin "15") (pinfunction "15_15") (pintype "passive"))
      (node (ref "U1") (pin "16") (pinfunction "GPIO12/RTC_GPIO12/TOUCH12/ADC2_CH1/FSPICLK/FSPIIO6/SUBSPICLK_16") (pintype "passive"))
    )
    (net (code "36") (name "/GPIO13") (class "Default")
      (node (ref "J1") (pin "16") (pinfunction "16_16") (pintype "passive"))
      (node (ref "U1") (pin "17") (pinfunction "GPIO13/RTC_GPIO13/TOUCH13/ADC2_CH2/FSPIQ/FSPIIO7/SUBSPIQ_17") (pintype "passive"))
    )
    (net (code "37") (name "/GPIO14") (class "Default")
      (node (ref "J1") (pin "17") (pinfunction "17_17") (pintype "passive"))
      (node (ref "U1") (pin "18") (pinfunction "GPIO14/RTC_GPIO14/TOUCH14/ADC2_CH3/FSPIWP/FSPIDQS/SUBSPIWP_18") (pintype "passive"))
    )
    (net (code "38") (name "/GPIO15") (class "Default")
      (node (ref "J1") (pin "18") (pinfunction "18_18") (pintype "passive"))
      (node (ref "U1") (pin "19") (pinfunction "GPIO15/RTC_GPIO15/U0RTS/ADC2_CH4/XTAL_32K_P_19") (pintype "passive"))
    )
    (net (code "39") (name "/GPIO16") (class "Default")
      (node (ref "J1") (pin "19") (pinfunction "19_19") (pintype "passive"))
      (node (ref "U1") (pin "20") (pinfunction "GPIO16/RTC_GPIO16/U0CTS/ADC2_CH5/XTAL_32K_N_20") (pintype "passive"))
    )
    (net (code "40") (name "/GPIO17") (class "Default")
      (node (ref "J1") (pin "20") (pinfunction "20_20") (pintype "passive"))
      (node (ref "U1") (pin "21") (pinfunction "GPIO17/RTC_GPIO17/U1TXD/ADC2_CH6_21") (pintype "passive"))
    )
    (net (code "41") (name "/GPIO18") (class "Default")
      (node (ref "J1") (pin "21") (pinfunction "21_21") (pintype "passive"))
      (node (ref "U1") (pin "22") (pinfunction "GPIO18/RTC_GPIO18/U1RXD/ADC2_CH7/CLK_OUT3_22") (pintype "passive"))
    )
    (net (code "42") (name "/GPIO21") (class "Default")
      (node (ref "J2") (pin "19") (pinfunction "19_19") (pintype "passive"))
      (node (ref "U1") (pin "25") (pinfunction "GPIO21/RTC_GPIO21_25") (pintype "passive"))
    )
    (net (code "43") (name "/GPIO26") (class "Default")
      (node (ref "J2") (pin "18") (pinfunction "18_18") (pintype "passive"))
      (node (ref "U1") (pin "26") (pinfunction "GPIO26/SPICS1_26") (pintype "passive"))
    )
    (net (code "44") (name "/GPIO33") (class "Default")
      (node (ref "J2") (pin "17") (pinfunction "17_17") (pintype "passive"))
      (node (ref "U1") (pin "28") (pinfunction "GPIO33/SPIIO4/FSPIHD/SUBSPIHD_28") (pintype "passive"))
    )
    (net (code "45") (name "/GPIO34") (class "Default")
      (node (ref "J2") (pin "16") (pinfunction "16_16") (pintype "passive"))
      (node (ref "U1") (pin "29") (pinfunction "GPIO34/SPIIO5/FSPICS0/SUBSPICS0_29") (pintype "passive"))
    )
    (net (code "46") (name "/GPIO35") (class "Default")
      (node (ref "J2") (pin "15") (pinfunction "15_15") (pintype "passive"))
      (node (ref "U1") (pin "31") (pinfunction "GPIO35/SPIIO6/FSPID/SUBSPID_31") (pintype "passive"))
    )
    (net (code "47") (name "/GPIO36") (class "Default")
      (node (ref "J2") (pin "14") (pinfunction "14_14") (pintype "passive"))
      (node (ref "U1") (pin "32") (pinfunction "GPIO36/SPIIO7/FSPICLK/SUBSPICLK_32") (pintype "passive"))
    )
    (net (code "48") (name "/GPIO37") (class "Default")
      (node (ref "J2") (pin "13") (pinfunction "13_13") (pintype "passive"))
      (node (ref "U1") (pin "33") (pinfunction "GPIO37/SPIDQS/FSPIQ/SUBSPIQ_33") (pintype "passive"))
    )
    (net (code "49") (name "/GPIO38") (class "Default")
      (node (ref "J2") (pin "12") (pinfunction "12_12") (pintype "passive"))
      (node (ref "U1") (pin "34") (pinfunction "GPIO38/FSPIWP/SUBSPIWP_34") (pintype "passive"))
    )
    (net (code "50") (name "/GPIO39") (class "Default")
      (node (ref "J2") (pin "11") (pinfunction "11_11") (pintype "passive"))
      (node (ref "U1") (pin "35") (pinfunction "GPIO39/MTCK/CLK_OUT3/SUBSPICS1_35") (pintype "passive"))
    )
    (net (code "51") (name "/GPIO40") (class "Default")
      (node (ref "J2") (pin "10") (pinfunction "10_10") (pintype "passive"))
      (node (ref "U1") (pin "36") (pinfunction "GPIO40/MTDO/CLK_OUT2_36") (pintype "passive"))
    )
    (net (code "52") (name "/GPIO41") (class "Default")
      (node (ref "J2") (pin "9") (pinfunction "9_9") (pintype "passive"))
      (node (ref "U1") (pin "37") (pinfunction "GPIO41/MTDI/CLK_OUT1_37") (pintype "passive"))
    )
    (net (code "53") (name "/GPIO42") (class "Default")
      (node (ref "J2") (pin "8") (pinfunction "8_8") (pintype "passive"))
      (node (ref "U1") (pin "38") (pinfunction "GPIO42/MTMS_38") (pintype "passive"))
    )
    (net (code "54") (name "/GPIO45") (class "Default")
      (node (ref "J2") (pin "5") (pinfunction "5_5") (pintype "passive"))
      (node (ref "U1") (pin "41") (pinfunction "GPIO45_41") (pintype "passive"))
    )
    (net (code "55") (name "/GPIO46") (class "Default")
      (node (ref "J2") (pin "4") (pinfunction "4_4") (pintype "passive"))
      (node (ref "U1") (pin "44") (pinfunction "GPIO46_44") (pintype "passive"))
    )
    (net (code "56") (name "/GPIO47") (class "Default")
      (node (ref "J2") (pin "23") (pinfunction "23_23") (pintype "passive"))
      (node (ref "U1") (pin "27") (pinfunction "GPIO47/SPICLK_P_DIFF/SUBSPICLK_P_DIFF_27") (pintype "passive"))
    )
    (net (code "57") (name "/GPIO48") (class "Default")
      (node (ref "J2") (pin "22") (pinfunction "22_22") (pintype "passive"))
      (node (ref "U1") (pin "30") (pinfunction "GPIO48/SPICLK_N_DIFF/_SUBSPICLK_N_DIFF_30") (pintype "passive"))
    )
    (net (code "58") (name "/RTS_FTDI") (class "Default")
      (node (ref "Q1") (pin "2") (pinfunction "E_2") (pintype "passive"))
      (node (ref "R17") (pin "1") (pinfunction "1_1") (pintype "passive"))
      (node (ref "U2") (pin "19") (pinfunction "~{RTS}_19") (pintype "passive"))
    )
    (net (code "59") (name "/RXD_FTDI") (class "Default")
      (node (ref "R18") (pin "2") (pinfunction "2_2") (pintype "passive"))
      (node (ref "U2") (pin "1") (pinfunction "RXD_1") (pintype "passive"))
    )
    (net (code "60") (name "/TXD_FTDI") (class "Default")
      (node (ref "R19") (pin "2") (pinfunction "2_2") (pintype "passive"))
      (node (ref "U2") (pin "17") (pinfunction "TXD_17") (pintype "passive"))
    )
    (net (code "61") (name "/U0RXD") (class "Default")
      (node (ref "J2") (pin "6") (pinfunction "6_6") (pintype "passive"))
      (node (ref "R19") (pin "1") (pinfunction "1_1") (pintype "passive"))
      (node (ref "U1") (pin "40") (pinfunction "GPIO44,_U0RXD,_CLK_OUT2_40") (pintype "passive"))
    )
    (net (code "62") (name "/U0TXD") (class "Default")
      (node (ref "J2") (pin "7") (pinfunction "7_7") (pintype "passive"))
      (node (ref "R18") (pin "1") (pinfunction "1_1") (pintype "passive"))
      (node (ref "U1") (pin "39") (pinfunction "GPIO43,_U0TXD,_CLK_OUT1_39") (pintype "passive"))
    )
    (net (code "63") (name "/VBUS_SENSE") (class "Default")
      (node (ref "R10") (pin "2") (pinfunction "2_2") (pintype "passive"))
      (node (ref "R13") (pin "2") (pinfunction "2_2") (pintype "passive"))
      (node (ref "U2") (pin "16") (pinfunction "CBUS3_16") (pintype "passive"))
    )
    (net (code "64") (name "GND") (class "Default")
      (node (ref "C1") (pin "2") (pinfunction "2_2") (pintype "passive"))
      (node (ref "C10") (pin "2") (pinfunction "2_2") (pintype "passive"))
      (node (ref "C11") (pin "1") (pinfunction "1_1") (pintype "passive"))
      (node (ref "C12") (pin "1") (pinfunction "1_1") (pintype "passive"))
      (node (ref "C13") (pin "1") (pinfunction "1_1") (pintype "passive"))
      (node (ref "C14") (pin "1") (pinfunction "1_1") (pintype "passive"))
      (node (ref "C15") (pin "2") (pinfunction "2_2") (pintype "passive"))
      (node (ref "C16") (pin "2") (pinfunction "2_2") (pintype "passive"))
      (node (ref "C17") (pin "2") (pinfunction "2_2") (pintype "passive"))
      (node (ref "C2") (pin "1") (pinfunction "1_1") (pintype "passive"))
      (node (ref "C3") (pin "2") (pinfunction "2_2") (pintype "passive"))
      (node (ref "C4") (pin "2") (pinfunction "2_2") (pintype "passive"))
      (node (ref "C5") (pin "2") (pinfunction "2_2") (pintype "passive"))
      (node (ref "C6") (pin "2") (pinfunction "2_2") (pintype "passive"))
      (node (ref "C7") (pin "2") (pinfunction "2_2") (pintype "passive"))
      (node (ref "C8") (pin "2") (pinfunction "2_2") (pintype "passive"))
      (node (ref "C9") (pin "2") (pinfunction "2_2") (pintype "passive"))
      (node (ref "D1") (pin "1") (pinfunction "1_1") (pintype "passive"))
      (node (ref "D3") (pin "2") (pinfunction "2_2") (pintype "passive"))
      (node (ref "D4") (pin "2") (pinfunction "2_2") (pintype "passive"))
      (node (ref "D5") (pin "2") (pinfunction "2_2") (pintype "passive"))
      (node (ref "D6") (pin "2") (pinfunction "2_2") (pintype "passive"))
      (node (ref "D7") (pin "2") (pinfunction "2_2") (pintype "passive"))
      (node (ref "D8") (pin "2") (pinfunction "2_2") (pintype "passive"))
      (node (ref "J1") (pin "1") (pinfunction "1_1") (pintype "passive"))
      (node (ref "J1") (pin "23") (pinfunction "23_23") (pintype "passive"))
      (node (ref "J2") (pin "2") (pinfunction "2_2") (pintype "passive"))
      (node (ref "J2") (pin "24") (pinfunction "24_24") (pintype "passive"))
      (node (ref "J3") (pin "A1B12") (pinfunction "GND_A1B12_A1B12") (pintype "passive"))
      (node (ref "J3") (pin "B1A12") (pinfunction "GND_B1A12_B1A12") (pintype "passive"))
      (node (ref "J3") (pin "S1") (pinfunction "SHIELD_1_S1") (pintype "passive"))
      (node (ref "J3") (pin "S2") (pinfunction "SHIELD_2_S2") (pintype "passive"))
      (node (ref "J3") (pin "S3") (pinfunction "SHIELD_3_S3") (pintype "passive"))
      (node (ref "J3") (pin "S4") (pinfunction "SHIELD_4_S4") (pintype "passive"))
      (node (ref "J4") (pin "A1B12") (pinfunction "GND_A1B12_A1B12") (pintype "passive"))
      (node (ref "J4") (pin "B1A12") (pinfunction "GND_B1A12_B1A12") (pintype "passive"))
      (node (ref "J4") (pin "S1") (pinfunction "SHIELD_1_S1") (pintype "passive"))
      (node (ref "J4") (pin "S2") (pinfunction "SHIELD_2_S2") (pintype "passive"))
      (node (ref "J4") (pin "S3") (pinfunction "SHIELD_3_S3") (pintype "passive"))
      (node (ref "J4") (pin "S4") (pinfunction "SHIELD_4_S4") (pintype "passive"))
      (node (ref "R11") (pin "1") (pinfunction "1_1") (pintype "passive"))
      (node (ref "R12") (pin "1") (pinfunction "1_1") (pintype "passive"))
      (node (ref "R13") (pin "1") (pinfunction "1_1") (pintype "passive"))
      (node (ref "R14") (pin "1") (pinfunction "1_1") (pintype "passive"))
      (node (ref "R15") (pin "1") (pinfunction "1_1") (pintype "passive"))
      (node (ref "R9") (pin "2") (pinfunction "2_2") (pintype "passive"))
      (node (ref "SW1") (pin "3") (pinfunction "3_3") (pintype "passive"))
      (node (ref "SW1") (pin "4") (pinfunction "4_4") (pintype "passive"))
      (node (ref "SW2") (pin "3") (pinfunction "3_3") (pintype "passive"))
      (node (ref "SW2") (pin "4") (pinfunction "4_4") (pintype "passive"))
      (node (ref "U1") (pin "1") (pinfunction "GND_01_1") (pintype "passive"))
      (node (ref "U1") (pin "2") (pinfunction "GND_02_2") (pintype "passive"))
      (node (ref "U1") (pin "42") (pinfunction "GND_42") (pintype "passive"))
      (node (ref "U1") (pin "43") (pinfunction "GND_43") (pintype "passive"))
      (node (ref "U1") (pin "46") (pinfunction "GND_46_46") (pintype "passive"))
      (node (ref "U1") (pin "47") (pinfunction "GND_47_47") (pintype "passive"))
      (node (ref "U1") (pin "48") (pinfunction "GND_48_48") (pintype "passive"))
      (node (ref "U1") (pin "49") (pinfunction "GND_49_49") (pintype "passive"))
      (node (ref "U1") (pin "50") (pinfunction "GND_50_50") (pintype "passive"))
      (node (ref "U1") (pin "51") (pinfunction "GND_51_51") (pintype "passive"))
      (node (ref "U1") (pin "52") (pinfunction "GND_52_52") (pintype "passive"))
      (node (ref "U1") (pin "53") (pinfunction "GND_53_53") (pintype "passive"))
      (node (ref "U1") (pin "54") (pinfunction "GND_54_54") (pintype "passive"))
      (node (ref "U1") (pin "55") (pinfunction "GND_55_55") (pintype "passive"))
      (node (ref "U1") (pin "56") (pinfunction "GND_56_56") (pintype "passive"))
      (node (ref "U1") (pin "57") (pinfunction "GND_57_57") (pintype "passive"))
      (node (ref "U1") (pin "58") (pinfunction "GND_58_58") (pintype "passive"))
      (node (ref "U1") (pin "59") (pinfunction "GND_59_59") (pintype "passive"))
      (node (ref "U1") (pin "60") (pinfunction "GND_60_60") (pintype "passive"))
      (node (ref "U1") (pin "61") (pinfunction "GND_61_61") (pintype "passive"))
      (node (ref "U1") (pin "62") (pinfunction "GND_62_62") (pintype "passive"))
      (node (ref "U1") (pin "63") (pinfunction "GND_63_63") (pintype "passive"))
      (node (ref "U1") (pin "64") (pinfunction "GND_64_64") (pintype "passive"))
      (node (ref "U1") (pin "65") (pinfunction "GND_65_65") (pintype "passive"))
      (node (ref "U1") (pin "66") (pinfunction "GND_66_66") (pintype "passive"))
      (node (ref "U1") (pin "67") (pinfunction "GND_67_67") (pintype "passive"))
      (node (ref "U1") (pin "68") (pinfunction "GND_68_68") (pintype "passive"))
      (node (ref "U1") (pin "69") (pinfunction "GND_69_69") (pintype "passive"))
      (node (ref "U1") (pin "70") (pinfunction "GND_70_70") (pintype "passive"))
      (node (ref "U1") (pin "71") (pinfunction "GND_71_71") (pintype "passive"))
      (node (ref "U1") (pin "72") (pinfunction "GND_72_72") (pintype "passive"))
      (node (ref "U1") (pin "73") (pinfunction "GND_73_73") (pintype "passive"))
      (node (ref "U2") (pin "13") (pinfunction "GND_13") (pintype "passive"))
      (node (ref "U2") (pin "21") (pinfunction "GND_21") (pintype "passive"))
      (node (ref "U2") (pin "3") (pinfunction "GND_3") (pintype "passive"))
      (node (ref "U3") (pin "2") (pinfunction "GND_2") (pintype "power_in"))
      (node (ref "U3") (pin "4") (pinfunction "GND_4") (pintype "power_in"))
    )
    (net (code "65") (name "Net-(D1-Pad2)") (class "Default")
      (node (ref "D1") (pin "2") (pinfunction "2_2") (pintype "passive"))
      (node (ref "R3") (pin "1") (pinfunction "1_1") (pintype "passive"))
    )
    (net (code "66") (name "Net-(D2-Pad2)") (class "Default")
      (node (ref "D2") (pin "2") (pinfunction "2_2") (pintype "passive"))
      (node (ref "R4") (pin "1") (pinfunction "1_1") (pintype "passive"))
    )
    (net (code "67") (name "Net-(J3-CC1)") (class "Default")
      (node (ref "J3") (pin "A5") (pinfunction "CC1_A5") (pintype "passive"))
      (node (ref "R12") (pin "2") (pinfunction "2_2") (pintype "passive"))
    )
    (net (code "68") (name "Net-(J3-CC2)") (class "Default")
      (node (ref "J3") (pin "B5") (pinfunction "CC2_B5") (pintype "passive"))
      (node (ref "R11") (pin "2") (pinfunction "2_2") (pintype "passive"))
    )
    (net (code "69") (name "Net-(J4-CC1)") (class "Default")
      (node (ref "J4") (pin "A5") (pinfunction "CC1_A5") (pintype "passive"))
      (node (ref "R15") (pin "2") (pinfunction "2_2") (pintype "passive"))
    )
    (net (code "70") (name "Net-(J4-CC2)") (class "Default")
      (node (ref "J4") (pin "B5") (pinfunction "CC2_B5") (pintype "passive"))
      (node (ref "R14") (pin "2") (pinfunction "2_2") (pintype "passive"))
    )
    (net (code "71") (name "Net-(Q1-B)") (class "Default")
      (node (ref "Q1") (pin "1") (pinfunction "B_1") (pintype "passive"))
      (node (ref "R16") (pin "2") (pinfunction "2_2") (pintype "passive"))
    )
    (net (code "72") (name "Net-(Q2-B)") (class "Default")
      (node (ref "Q2") (pin "1") (pinfunction "B_1") (pintype "passive"))
      (node (ref "R17") (pin "2") (pinfunction "2_2") (pintype "passive"))
    )
    (net (code "73") (name "Net-(U2-CBUS0)") (class "Default")
      (node (ref "R9") (pin "1") (pinfunction "1_1") (pintype "passive"))
      (node (ref "U2") (pin "15") (pinfunction "CBUS0_15") (pintype "passive"))
    )
    (net (code "74") (name "unconnected-(J1-Pad24)") (class "Default")
      (node (ref "J1") (pin "24") (pinfunction "24_24") (pintype "passive+no_connect"))
    )
    (net (code "75") (name "unconnected-(J3-SBU1-PadA8)") (class "Default")
      (node (ref "J3") (pin "A8") (pinfunction "SBU1_A8") (pintype "passive+no_connect"))
    )
    (net (code "76") (name "unconnected-(J3-SBU2-PadB8)") (class "Default")
      (node (ref "J3") (pin "B8") (pinfunction "SBU2_B8") (pintype "passive+no_connect"))
    )
    (net (code "77") (name "unconnected-(J4-SBU1-PadA8)") (class "Default")
      (node (ref "J4") (pin "A8") (pinfunction "SBU1_A8") (pintype "passive+no_connect"))
    )
    (net (code "78") (name "unconnected-(J4-SBU2-PadB8)") (class "Default")
      (node (ref "J4") (pin "B8") (pinfunction "SBU2_B8") (pintype "passive+no_connect"))
    )
    (net (code "79") (name "unconnected-(U2-CBUS1-Pad14)") (class "Default")
      (node (ref "U2") (pin "14") (pinfunction "CBUS1_14") (pintype "passive+no_connect"))
    )
    (net (code "80") (name "unconnected-(U2-CBUS2-Pad7)") (class "Default")
      (node (ref "U2") (pin "7") (pinfunction "CBUS2_7") (pintype "passive+no_connect"))
    )
    (net (code "81") (name "unconnected-(U2-~{CTS}-Pad6)") (class "Default")
      (node (ref "U2") (pin "6") (pinfunction "~{CTS}_6") (pintype "passive+no_connect"))
    )
    (net (code "82") (name "unconnected-(U2-~{DCD}-Pad5)") (class "Default")
      (node (ref "U2") (pin "5") (pinfunction "~{DCD}_5") (pintype "passive+no_connect"))
    )
    (net (code "83") (name "unconnected-(U2-~{DSR}-Pad4)") (class "Default")
      (node (ref "U2") (pin "4") (pinfunction "~{DSR}_4") (pintype "passive+no_connect"))
    )
    (net (code "84") (name "unconnected-(U2-~{RI}-Pad2)") (class "Default")
      (node (ref "U2") (pin "2") (pinfunction "~{RI}_2") (pintype "passive+no_connect"))
    )
  )
)
